# Kelpie_Pi_hat_Schematic.net
KiCad netlist of a schematic drawn in Altium Designer
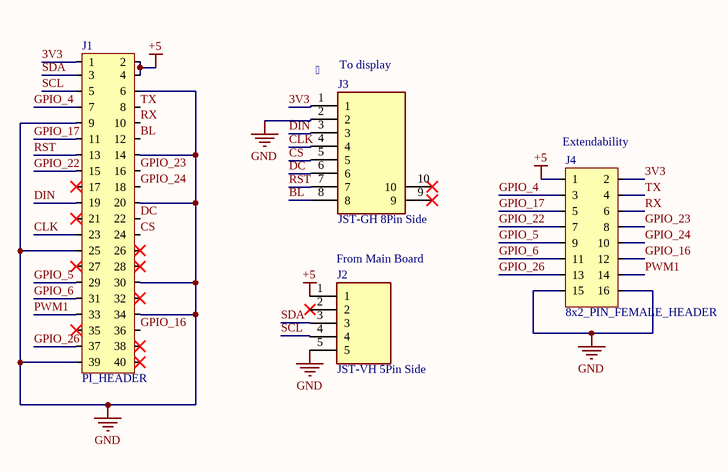
[diagram p0: Kelpie_Pi_hat_Schematic.SchDoc]

(export (version "E")
  (design (tool "Eeschema 10.0.6"))
  (components
    (comp (ref "J1")
      (value "PI_HEADER")
      (footprint "PI_HEADER")
      (description "40 Pin (20x2) Pi Header (Adafruit 2243)")
      (libsource (lib "Kelpie_Pi_Hat_Schematic_Lib") (part "PI_HEADER"))
    )
    (comp (ref "J2")
      (value "JST-VH 5Pin Side")
      (footprint "SamacSys:B5PSVHLFSN")
      (description "Connector")
      (fields (field (name "MANUFACTURER_PART_NUMBER") "B5PS-VH(LF)(SN)"))
      (libsource (lib "*") (part "B5PS-VH_LF__SN_"))
    )
    (comp (ref "J3")
      (value "JST-GH 8Pin Side")
      (footprint "SamacSys:BM08BGHSTBTLFSN")
      (description "Connector")
      (fields (field (name "MANUFACTURER_PART_NUMBER") "BM08B-GHS-TBT(LF)(SN)"))
      (libsource (lib "*") (part "BM08B-GHS-TBT_LF__SN_"))
    )
    (comp (ref "J4")
      (value "8x2_PIN_FEMALE_HEADER")
      (footprint "8x2_PIN_FEMALE_HEADER")
      (description "https://core-electronics.com.au/0-100-2-54-mm-female-header-2x8-pin-straight.html")
      (libsource (lib "Kelpie_Pi_Hat_Schematic_Lib") (part "8x2_PIN_FEMALE_HEADER"))
    )
  )
  (nets
    (net (code "1") (name "+5") (class "Default")
      (node (ref "J1") (pin "2") (pinfunction "2_2") (pintype "passive"))
      (node (ref "J1") (pin "4") (pinfunction "4_4") (pintype "passive"))
      (node (ref "J2") (pin "1") (pinfunction "1_1") (pintype "passive"))
      (node (ref "J4") (pin "1") (pinfunction "1_1") (pintype "passive"))
    )
    (net (code "2") (name "/3V3") (class "Default")
      (node (ref "J1") (pin "1") (pinfunction "1_1") (pintype "passive"))
      (node (ref "J3") (pin "1") (pinfunction "1_1") (pintype "passive"))
      (node (ref "J4") (pin "2") (pinfunction "2_2") (pintype "passive"))
    )
    (net (code "3") (name "/BL") (class "Default")
      (node (ref "J1") (pin "12") (pinfunction "12_12") (pintype "passive"))
      (node (ref "J3") (pin "8") (pinfunction "8_8") (pintype "passive"))
    )
    (net (code "4") (name "/CLK") (class "Default")
      (node (ref "J1") (pin "23") (pinfunction "23_23") (pintype "passive"))
      (node (ref "J3") (pin "4") (pinfunction "4_4") (pintype "passive"))
    )
    (net (code "5") (name "/CS") (class "Default")
      (node (ref "J1") (pin "24") (pinfunction "24_24") (pintype "passive"))
      (node (ref "J3") (pin "5") (pinfunction "5_5") (pintype "passive"))
    )
    (net (code "6") (name "/DC") (class "Default")
      (node (ref "J1") (pin "22") (pinfunction "22_22") (pintype "passive"))
      (node (ref "J3") (pin "6") (pinfunction "6_6") (pintype "passive"))
    )
    (net (code "7") (name "/DIN") (class "Default")
      (node (ref "J1") (pin "19") (pinfunction "19_19") (pintype "passive"))
      (node (ref "J3") (pin "3") (pinfunction "3_3") (pintype "passive"))
    )
    (net (code "8") (name "/GPIO_4") (class "Default")
      (node (ref "J1") (pin "7") (pinfunction "7_7") (pintype "passive"))
      (node (ref "J4") (pin "3") (pinfunction "3_3") (pintype "passive"))
    )
    (net (code "9") (name "/GPIO_5") (class "Default")
      (node (ref "J1") (pin "29") (pinfunction "29_29") (pintype "passive"))
      (node (ref "J4") (pin "9") (pinfunction "9_9") (pintype "passive"))
    )
    (net (code "10") (name "/GPIO_6") (class "Default")
      (node (ref "J1") (pin "31") (pinfunction "31_31") (pintype "passive"))
      (node (ref "J4") (pin "11") (pinfunction "11_11") (pintype "passive"))
    )
    (net (code "11") (name "/GPIO_16") (class "Default")
      (node (ref "J1") (pin "36") (pinfunction "36_36") (pintype "passive"))
      (node (ref "J4") (pin "12") (pinfunction "12_12") (pintype "passive"))
    )
    (net (code "12") (name "/GPIO_17") (class "Default")
      (node (ref "J1") (pin "11") (pinfunction "11_11") (pintype "passive"))
      (node (ref "J4") (pin "5") (pinfunction "5_5") (pintype "passive"))
    )
    (net (code "13") (name "/GPIO_22") (class "Default")
      (node (ref "J1") (pin "15") (pinfunction "15_15") (pintype "passive"))
      (node (ref "J4") (pin "7") (pinfunction "7_7") (pintype "passive"))
    )
    (net (code "14") (name "/GPIO_23") (class "Default")
      (node (ref "J1") (pin "16") (pinfunction "16_16") (pintype "passive"))
      (node (ref "J4") (pin "8") (pinfunction "8_8") (pintype "passive"))
    )
    (net (code "15") (name "/GPIO_24") (class "Default")
      (node (ref "J1") (pin "18") (pinfunction "18_18") (pintype "passive"))
      (node (ref "J4") (pin "10") (pinfunction "10_10") (pintype "passive"))
    )
    (net (code "16") (name "/GPIO_26") (class "Default")
      (node (ref "J1") (pin "37") (pinfunction "37_37") (pintype "passive"))
      (node (ref "J4") (pin "13") (pinfunction "13_13") (pintype "passive"))
    )
    (net (code "17") (name "/PWM1") (class "Default")
      (node (ref "J1") (pin "33") (pinfunction "33_33") (pintype "passive"))
      (node (ref "J4") (pin "14") (pinfunction "14_14") (pintype "passive"))
    )
    (net (code "18") (name "/RST") (class "Default")
      (node (ref "J1") (pin "13") (pinfunction "13_13") (pintype "passive"))
      (node (ref "J3") (pin "7") (pinfunction "7_7") (pintype "passive"))
    )
    (net (code "19") (name "/RX") (class "Default")
      (node (ref "J1") (pin "10") (pinfunction "10_10") (pintype "passive"))
      (node (ref "J4") (pin "6") (pinfunction "6_6") (pintype "passive"))
    )
    (net (code "20") (name "/SCL") (class "Default")
      (node (ref "J1") (pin "5") (pinfunction "5_5") (pintype "passive"))
      (node (ref "J2") (pin "4") (pinfunction "4_4") (pintype "passive"))
    )
    (net (code "21") (name "/SDA") (class "Default")
      (node (ref "J1") (pin "3") (pinfunction "3_3") (pintype "passive"))
      (node (ref "J2") (pin "3") (pinfunction "3_3") (pintype "passive"))
    )
    (net (code "22") (name "/TX") (class "Default")
      (node (ref "J1") (pin "8") (pinfunction "8_8") (pintype "passive"))
      (node (ref "J4") (pin "4") (pinfunction "4_4") (pintype "passive"))
    )
    (net (code "23") (name "GND") (class "Default")
      (node (ref "J1") (pin "14") (pinfunction "14_14") (pintype "passive"))
      (node (ref "J1") (pin "20") (pinfunction "20_20") (pintype "passive"))
      (node (ref "J1") (pin "25") (pinfunction "25_25") (pintype "passive"))
      (node (ref "J1") (pin "30") (pinfunction "30_30") (pintype "passive"))
      (node (ref "J1") (pin "34") (pinfunction "34_34") (pintype "passive"))
      (node (ref "J1") (pin "39") (pinfunction "39_39") (pintype "passive"))
      (node (ref "J1") (pin "6") (pinfunction "6_6") (pintype "passive"))
      (node (ref "J1") (pin "9") (pinfunction "9_9") (pintype "passive"))
      (node (ref "J2") (pin "5") (pinfunction "5_5") (pintype "passive"))
      (node (ref "J3") (pin "2") (pinfunction "2_2") (pintype "passive"))
      (node (ref "J4") (pin "15") (pinfunction "15_15") (pintype "passive"))
      (node (ref "J4") (pin "16") (pinfunction "16_16") (pintype "passive"))
    )
    (net (code "24") (name "unconnected-(J1-Pad17)") (class "Default")
      (node (ref "J1") (pin "17") (pinfunction "17_17") (pintype "passive+no_connect"))
    )
    (net (code "25") (name "unconnected-(J1-Pad21)") (class "Default")
      (node (ref "J1") (pin "21") (pinfunction "21_21") (pintype "passive+no_connect"))
    )
    (net (code "26") (name "unconnected-(J1-Pad26)") (class "Default")
      (node (ref "J1") (pin "26") (pinfunction "26_26") (pintype "passive+no_connect"))
    )
    (net (code "27") (name "unconnected-(J1-Pad27)") (class "Default")
      (node (ref "J1") (pin "27") (pinfunction "27_27") (pintype "passive+no_connect"))
    )
    (net (code "28") (name "unconnected-(J1-Pad28)") (class "Default")
      (node (ref "J1") (pin "28") (pinfunction "28_28") (pintype "passive+no_connect"))
    )
    (net (code "29") (name "unconnected-(J1-Pad32)") (class "Default")
      (node (ref "J1") (pin "32") (pinfunction "32_32") (pintype "passive+no_connect"))
    )
    (net (code "30") (name "unconnected-(J1-Pad35)") (class "Default")
      (node (ref "J1") (pin "35") (pinfunction "35_35") (pintype "passive+no_connect"))
    )
    (net (code "31") (name "unconnected-(J1-Pad38)") (class "Default")
      (node (ref "J1") (pin "38") (pinfunction "38_38") (pintype "passive+no_connect"))
    )
    (net (code "32") (name "unconnected-(J1-Pad40)") (class "Default")
      (node (ref "J1") (pin "40") (pinfunction "40_40") (pintype "passive+no_connect"))
    )
    (net (code "33") (name "unconnected-(J2-Pad2)") (class "Default")
      (node (ref "J2") (pin "2") (pinfunction "2_2") (pintype "passive+no_connect"))
    )
    (net (code "34") (name "unconnected-(J3-Pad9)") (class "Default")
      (node (ref "J3") (pin "9") (pinfunction "9_9") (pintype "passive+no_connect"))
    )
    (net (code "35") (name "unconnected-(J3-Pad10)") (class "Default")
      (node (ref "J3") (pin "10") (pinfunction "10_10") (pintype "passive+no_connect"))
    )
  )
)
